# PCB-Rpi.net
KiCad netlist of a schematic drawn in EAGLE
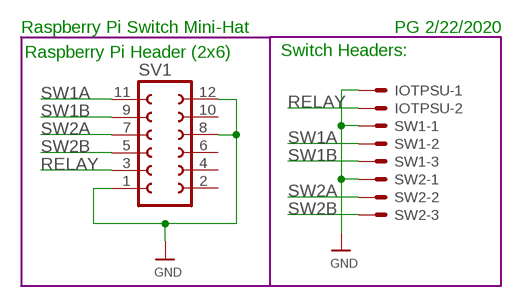
[diagram p0: schematic, sheet 1]

(export (version "E")
  (design (tool "Eeschema 10.0.6"))
  (components
    (comp (ref "IOTPSU")
      (value "KK-156-2")
      (footprint "eagle-import:KK-156-2")
      (fields (field (name "MF") "MOLEX"))
      (libsource (lib "eagle-import") (part "KK-156-2"))
    )
    (comp (ref "SV1")
      (value "FE06-2")
      (footprint "eagle-import:FE06-2")
      (libsource (lib "eagle-import") (part "FE06-2"))
    )
    (comp (ref "SW1")
      (value "KK-156-3")
      (footprint "eagle-import:KK-156-3")
      (fields (field (name "MF") "MOLEX"))
      (libsource (lib "eagle-import") (part "KK-156-3"))
    )
    (comp (ref "SW2")
      (value "KK-156-3")
      (footprint "eagle-import:KK-156-3")
      (fields (field (name "MF") "MOLEX"))
      (libsource (lib "eagle-import") (part "KK-156-3"))
    )
  )
  (nets
    (net (code "1") (name "/RELAY") (class "Default")
      (node (ref "IOTPSU") (pin "2") (pinfunction "S_2") (pintype "passive"))
      (node (ref "SV1") (pin "3") (pinfunction "3_3") (pintype "passive"))
    )
    (net (code "2") (name "/SW1A") (class "Default")
      (node (ref "SV1") (pin "11") (pinfunction "11_11") (pintype "passive"))
      (node (ref "SW1") (pin "2") (pinfunction "S_2") (pintype "passive"))
    )
    (net (code "3") (name "/SW1B") (class "Default")
      (node (ref "SV1") (pin "9") (pinfunction "9_9") (pintype "passive"))
      (node (ref "SW1") (pin "3") (pinfunction "S_3") (pintype "passive"))
    )
    (net (code "4") (name "/SW2A") (class "Default")
      (node (ref "SV1") (pin "7") (pinfunction "7_7") (pintype "passive"))
      (node (ref "SW2") (pin "2") (pinfunction "S_2") (pintype "passive"))
    )
    (net (code "5") (name "/SW2B") (class "Default")
      (node (ref "SV1") (pin "5") (pinfunction "5_5") (pintype "passive"))
      (node (ref "SW2") (pin "3") (pinfunction "S_3") (pintype "passive"))
    )
    (net (code "6") (name "GND") (class "Default")
      (node (ref "IOTPSU") (pin "1") (pinfunction "S_1") (pintype "passive"))
      (node (ref "SV1") (pin "1") (pinfunction "1_1") (pintype "passive"))
      (node (ref "SV1") (pin "12") (pinfunction "12_12") (pintype "passive"))
      (node (ref "SV1") (pin "8") (pinfunction "8_8") (pintype "passive"))
      (node (ref "SW1") (pin "1") (pinfunction "S_1") (pintype "passive"))
      (node (ref "SW2") (pin "1") (pinfunction "S_1") (pintype "passive"))
    )
    (net (code "7") (name "unconnected-(SV1-Pad2)") (class "Default")
      (node (ref "SV1") (pin "2") (pinfunction "2_2") (pintype "passive"))
    )
    (net (code "8") (name "unconnected-(SV1-Pad4)") (class "Default")
      (node (ref "SV1") (pin "4") (pinfunction "4_4") (pintype "passive"))
    )
    (net (code "9") (name "unconnected-(SV1-Pad6)") (class "Default")
      (node (ref "SV1") (pin "6") (pinfunction "6_6") (pintype "passive"))
    )
    (net (code "10") (name "unconnected-(SV1-Pad10)") (class "Default")
      (node (ref "SV1") (pin "10") (pinfunction "10_10") (pintype "passive"))
    )
  )
)
